# 1_Power.net
KiCad netlist of a schematic drawn in Altium Designer
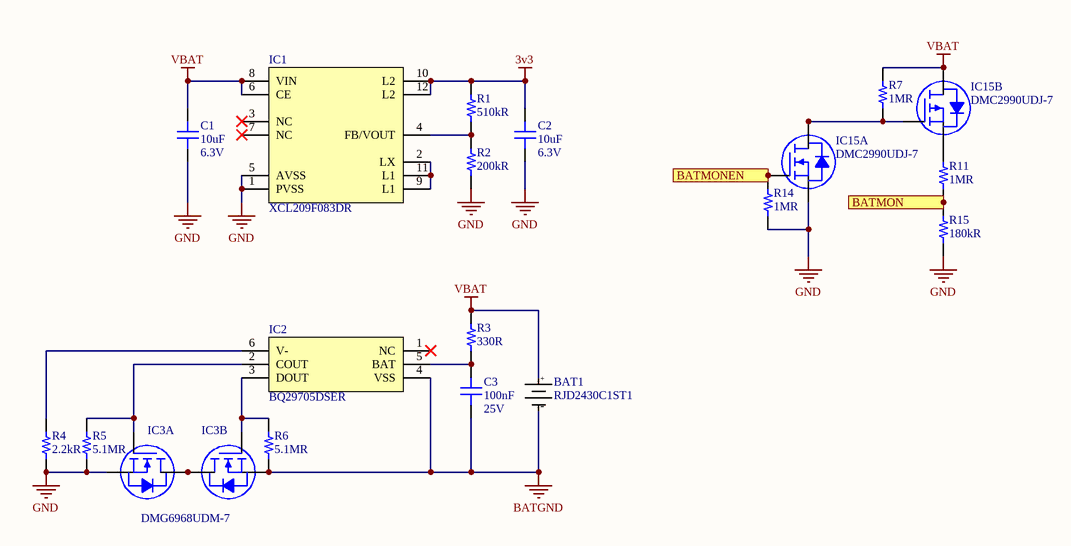
[diagram p0: [1] Power.SchDoc]

(export (version "E")
  (design (tool "Eeschema 10.0.6"))
  (components
    (comp (ref "BAT1")
      (value "RJD2430C1ST1")
      (footprint "ILLINOIS RJD2430C1ST1")
      (fields (field (name "MANUFACTURER") "Cornell Dubilier"))
      (libsource (lib "yildizIoT Library") (part "ILLINOIS RJD2430C1ST1"))
    )
    (comp (ref "C1")
      (value "10uF")
      (footprint "CAP 0402/1005")
      (description "0402 10 uF 6.3 V ±20 % Tolerance X5R Surface Mount Multilayer Ceramic Capacitor")
      (fields
        (field (name "MANUFACTURER") "Murata")
        (field (name "MANUFACTURER PART NUMBER") "GRM155R60J106ME15D")
        (field (name "VOLTAGE RATING") "6.3V")
      )
      (libsource (lib "yildizIoT Library") (part "Capacitor - Ceramic"))
    )
    (comp (ref "C2")
      (value "10uF")
      (footprint "CAP 0402/1005")
      (description "0402 10 uF 6.3 V ±20 % Tolerance X5R Surface Mount Multilayer Ceramic Capacitor")
      (fields
        (field (name "MANUFACTURER") "Murata")
        (field (name "MANUFACTURER PART NUMBER") "GRM155R60J106ME15D")
        (field (name "VOLTAGE RATING") "6.3V")
      )
      (libsource (lib "yildizIoT Library") (part "Capacitor - Ceramic"))
    )
    (comp (ref "C3")
      (value "100nF")
      (footprint "CAP 0402/1005")
      (description "Cap Ceramic 0.1uF 25V X5R 10% Pad SMD 0402 85°C T/R / Multi Layer Ceramic Capacitor (MLCC)")
      (fields
        (field (name "MANUFACTURER") "Samsung")
        (field (name "MANUFACTURER PART NUMBER") "CL05A104KA5NNNC")
        (field (name "VOLTAGE RATING (DC)") "25V")
      )
      (libsource (lib "yildizIoT Library") (part "Capacitor - Ceramic"))
    )
    (comp (ref "IC1")
      (value "XCL209F083DR")
      (footprint "TOREX XCL209F083DR")
      (description "Conv DC-DC 1.8V to 6V Step Down Single-Out 0.9V to 6V 0.4A 8-Pin USP-10B03")
      (fields (field (name "MANUFACTURER") "Torex"))
      (libsource (lib "yildizIoT Library") (part "TOREX XCL209F083DR"))
    )
    (comp (ref "IC2")
      (value "BQ29705DSER")
      (footprint "TI S-PDSO-N6 150x150x80")
      (description "Li-Ion/Li Polymer Advanced Single-Cell Battery Protector IC Family 6-WSON -40 to 85")
      (fields (field (name "MANUFACTURER") "Texas Instruments"))
      (libsource (lib "yildizIoT Library") (part "TI BQ29705"))
    )
    (comp (ref "IC3")
      (value "DMG6968UDM-7")
      (footprint "DIODES SOT-26-6")
      (description "Transistor MOSFET Array Dual N-CH 20V 6.5A 6-Pin SOT-26 T/R")
      (fields (field (name "MANUFACTURER") "Diodes"))
      (libsource (lib "yildizIoT Library") (part "DIODES DMG6968"))
    )
    (comp (ref "IC15")
      (value "DMC2990UDJ-7")
      (footprint "DIODE SOT-563")
      (description "Trans MOSFET N/P-CH 20V 0.45A/0.31A Automotive 6-Pin SOT-963 T/R")
      (fields (field (name "MANUFACTURER") "Diodes"))
      (libsource (lib "yildizIoT Library") (part "DIODES DMC2400"))
    )
    (comp (ref "R1")
      (value "510kR")
      (footprint "RES 0402/1005")
      (description "Surface Mount Chip Resistor, Thick Film, RC Series, 510 kohm, 63 mW, 1%, 50 V, 0402 [1005 Metric]")
      (fields
        (field (name "MANUFACTURER") "Yageo")
        (field (name "MANUFACTURER PART NUMBER") "RC0402FR-07510KL")
      )
      (libsource (lib "yildizIoT Library") (part "Resistor_Chip"))
    )
    (comp (ref "R2")
      (value "200kR")
      (footprint "RES 0402/1005")
      (description "Res General Purpose Thick Film 0402 200K Ohm 1% 1/16W ±100ppm/°C Molded SMD Paper T/R")
      (fields
        (field (name "MANUFACTURER") "Yageo")
        (field (name "MANUFACTURER PART NUMBER") "RC0402FR-07200KL")
      )
      (libsource (lib "yildizIoT Library") (part "Resistor_Chip"))
    )
    (comp (ref "R3")
      (value "330R")
      (footprint "RES 0402/1005 RF")
      (description "Res Thick Film 0402 330 Ohm 1% 0.063W(1/16W) ±100ppm/C Pad SMD T/R")
      (fields
        (field (name "MANUFACTURER") "Walsin Technologies")
        (field (name "MANUFACTURER PART NUMBER") "WR04X3300FTL")
      )
      (libsource (lib "yildizIoT Library") (part "Resistor_Chip"))
    )
    (comp (ref "R4")
      (value "2.2kR")
      (footprint "RES 0402/1005 RF")
      (description "Res General Purpose Thick Film 0402 2.2k Ohm 1% 1/16W ±100ppm/°C Molded Paper T/R")
      (fields
        (field (name "MANUFACTURER") "TE Connectivity")
        (field (name "MANUFACTURER PART NUMBER") "CRGCQ0402F2K2")
      )
      (libsource (lib "yildizIoT Library") (part "Resistor_Chip"))
    )
    (comp (ref "R5")
      (value "5.1MR")
      (footprint "RES 0402/1005")
      (description "Res Thick Film 0402 5.1M Ohm 1% 0.063W ±200ppm/°C Molded SMD Paper T/R")
      (fields
        (field (name "MANUFACTURER") "Stackpole Electronics")
        (field (name "MANUFACTURER PART NUMBER") "RMCF0402FT5M10")
      )
      (libsource (lib "yildizIoT Library") (part "Resistor_Chip"))
    )
    (comp (ref "R6")
      (value "5.1MR")
      (footprint "RES 0402/1005")
      (description "Res Thick Film 0402 5.1M Ohm 1% 0.063W ±200ppm/°C Molded SMD Paper T/R")
      (fields
        (field (name "MANUFACTURER") "Stackpole Electronics")
        (field (name "MANUFACTURER PART NUMBER") "RMCF0402FT5M10")
      )
      (libsource (lib "yildizIoT Library") (part "Resistor_Chip"))
    )
    (comp (ref "R7")
      (value "1MR")
      (footprint "RES 0402/1005 RF")
      (description "Res Thick Film 0402 1M Ohm 1% 0.063W(1/16W) ±100ppm/C Pad SMD Automotive T/R")
      (fields
        (field (name "MANUFACTURER") "TE Connectivity")
        (field (name "MANUFACTURER PART NUMBER") "CRGCQ0402F1M0")
      )
      (libsource (lib "yildizIoT Library") (part "Resistor_Chip"))
    )
    (comp (ref "R11")
      (value "1MR")
      (footprint "RES 0402/1005 RF")
      (description "Res Thick Film 0402 1M Ohm 1% 0.063W(1/16W) ±100ppm/C Pad SMD Automotive T/R")
      (fields
        (field (name "MANUFACTURER") "TE Connectivity")
        (field (name "MANUFACTURER PART NUMBER") "CRGCQ0402F1M0")
      )
      (libsource (lib "yildizIoT Library") (part "Resistor_Chip"))
    )
    (comp (ref "R14")
      (value "1MR")
      (footprint "RES 0402/1005 RF")
      (description "Res Thick Film 0402 1M Ohm 1% 0.063W(1/16W) ±100ppm/C Pad SMD Automotive T/R")
      (fields
        (field (name "MANUFACTURER") "TE Connectivity")
        (field (name "MANUFACTURER PART NUMBER") "CRGCQ0402F1M0")
      )
      (libsource (lib "yildizIoT Library") (part "Resistor_Chip"))
    )
    (comp (ref "R15")
      (value "180kR")
      (footprint "RES 0402/1005 RF")
      (description "Res General Purpose Thick Film 0402 180k Ohm 1% 1/16W ±100ppm/°C Molded Paper T/R")
      (fields
        (field (name "MANUFACTURER") "TE Connectivity")
        (field (name "MANUFACTURER PART NUMBER") "CRGCQ0402F180K")
      )
      (libsource (lib "yildizIoT Library") (part "Resistor_Chip"))
    )
  )
  (nets
    (net (code "1") (name "/BATMON") (class "Default")
      (node (ref "R11") (pin "1") (pinfunction "1_1") (pintype "passive"))
      (node (ref "R15") (pin "2") (pinfunction "2_2") (pintype "passive"))
    )
    (net (code "2") (name "/BATMONEN") (class "Default")
      (node (ref "IC15") (pin "6") (pinfunction "G1_6") (pintype "passive"))
      (node (ref "R14") (pin "2") (pinfunction "2_2") (pintype "passive"))
    )
    (net (code "3") (name "3v3") (class "Default")
      (node (ref "C2") (pin "2") (pinfunction "2_2") (pintype "passive"))
      (node (ref "IC1") (pin "10") (pinfunction "L2_10") (pintype "passive"))
      (node (ref "IC1") (pin "12") (pinfunction "L2_12") (pintype "passive"))
      (node (ref "R1") (pin "2") (pinfunction "2_2") (pintype "passive"))
    )
    (net (code "4") (name "BATGND") (class "Default")
      (node (ref "BAT1") (pin "2") (pinfunction "-_2") (pintype "passive"))
      (node (ref "C3") (pin "1") (pinfunction "1_1") (pintype "passive"))
      (node (ref "IC2") (pin "4") (pinfunction "VSS_4") (pintype "passive"))
      (node (ref "IC3") (pin "3") (pinfunction "S2_3") (pintype "passive"))
      (node (ref "R6") (pin "1") (pinfunction "1_1") (pintype "passive"))
    )
    (net (code "5") (name "GND") (class "Default")
      (node (ref "C1") (pin "1") (pinfunction "1_1") (pintype "passive"))
      (node (ref "C2") (pin "1") (pinfunction "1_1") (pintype "passive"))
      (node (ref "IC1") (pin "1") (pinfunction "PVSS_1") (pintype "passive"))
      (node (ref "IC1") (pin "5") (pinfunction "AVSS_5") (pintype "passive"))
      (node (ref "IC15") (pin "1") (pinfunction "S1_1") (pintype "passive"))
      (node (ref "IC3") (pin "1") (pinfunction "S1_1") (pintype "passive"))
      (node (ref "R14") (pin "1") (pinfunction "1_1") (pintype "passive"))
      (node (ref "R15") (pin "1") (pinfunction "1_1") (pintype "passive"))
      (node (ref "R2") (pin "1") (pinfunction "1_1") (pintype "passive"))
      (node (ref "R4") (pin "1") (pinfunction "1_1") (pintype "passive"))
      (node (ref "R5") (pin "1") (pinfunction "1_1") (pintype "passive"))
    )
    (net (code "6") (name "Net-(IC1-FB{slash}VOUT)") (class "Default")
      (node (ref "IC1") (pin "4") (pinfunction "FB/VOUT_4") (pintype "passive"))
      (node (ref "R1") (pin "1") (pinfunction "1_1") (pintype "passive"))
      (node (ref "R2") (pin "2") (pinfunction "2_2") (pintype "passive"))
    )
    (net (code "7") (name "Net-(IC1-LX)") (class "Default")
      (node (ref "IC1") (pin "11") (pinfunction "L1_11") (pintype "passive"))
      (node (ref "IC1") (pin "2") (pinfunction "LX_2") (pintype "passive"))
      (node (ref "IC1") (pin "9") (pinfunction "L1_9") (pintype "passive"))
    )
    (net (code "8") (name "Net-(IC2-BAT)") (class "Default")
      (node (ref "C3") (pin "2") (pinfunction "2_2") (pintype "passive"))
      (node (ref "IC2") (pin "5") (pinfunction "BAT_5") (pintype "passive"))
      (node (ref "R3") (pin "1") (pinfunction "1_1") (pintype "passive"))
    )
    (net (code "9") (name "Net-(IC2-COUT)") (class "Default")
      (node (ref "IC2") (pin "2") (pinfunction "COUT_2") (pintype "passive"))
      (node (ref "IC3") (pin "6") (pinfunction "G1_6") (pintype "passive"))
      (node (ref "R5") (pin "2") (pinfunction "2_2") (pintype "passive"))
    )
    (net (code "10") (name "Net-(IC2-DOUT)") (class "Default")
      (node (ref "IC2") (pin "3") (pinfunction "DOUT_3") (pintype "passive"))
      (node (ref "IC3") (pin "4") (pinfunction "G2_4") (pintype "passive"))
      (node (ref "R6") (pin "2") (pinfunction "2_2") (pintype "passive"))
    )
    (net (code "11") (name "Net-(IC2-V-)") (class "Default")
      (node (ref "IC2") (pin "6") (pinfunction "V-_6") (pintype "passive"))
      (node (ref "R4") (pin "2") (pinfunction "2_2") (pintype "passive"))
    )
    (net (code "12") (name "Net-(IC3A-D1-Pad2)") (class "Default")
      (node (ref "IC3") (pin "2") (pinfunction "D1_2") (pintype "passive"))
      (node (ref "IC3") (pin "5") (pinfunction "D1_5") (pintype "passive"))
    )
    (net (code "13") (name "Net-(IC15B-G2)") (class "Default")
      (node (ref "IC15") (pin "2") (pinfunction "D1_2") (pintype "passive"))
      (node (ref "IC15") (pin "4") (pinfunction "G2_4") (pintype "passive"))
      (node (ref "IC15") (pin "5") (pinfunction "D1_5") (pintype "passive"))
      (node (ref "R7") (pin "1") (pinfunction "1_1") (pintype "passive"))
    )
    (net (code "14") (name "Net-(IC15B-S2)") (class "Default")
      (node (ref "IC15") (pin "3") (pinfunction "S2_3") (pintype "passive"))
      (node (ref "R11") (pin "2") (pinfunction "2_2") (pintype "passive"))
    )
    (net (code "15") (name "VBAT") (class "Default")
      (node (ref "BAT1") (pin "1") (pinfunction "+_1") (pintype "passive"))
      (node (ref "C1") (pin "2") (pinfunction "2_2") (pintype "passive"))
      (node (ref "IC1") (pin "6") (pinfunction "CE_6") (pintype "passive"))
      (node (ref "IC1") (pin "8") (pinfunction "VIN_8") (pintype "passive"))
      (node (ref "IC15") (pin "5") (pinfunction "D2_5") (pintype "passive"))
      (node (ref "IC15") (pin "6") (pinfunction "D2_6") (pintype "passive"))
      (node (ref "R3") (pin "2") (pinfunction "2_2") (pintype "passive"))
      (node (ref "R7") (pin "2") (pinfunction "2_2") (pintype "passive"))
    )
    (net (code "16") (name "unconnected-(IC1-NC-Pad3)") (class "Default")
      (node (ref "IC1") (pin "3") (pinfunction "NC_3") (pintype "passive+no_connect"))
    )
    (net (code "17") (name "unconnected-(IC1-NC-Pad7)") (class "Default")
      (node (ref "IC1") (pin "7") (pinfunction "NC_7") (pintype "passive+no_connect"))
    )
    (net (code "18") (name "unconnected-(IC2-NC-Pad1)") (class "Default")
      (node (ref "IC2") (pin "1") (pinfunction "NC_1") (pintype "passive+no_connect"))
    )
  )
)
